# RC-car-Adruino.net
KiCad netlist of a schematic drawn in EAGLE
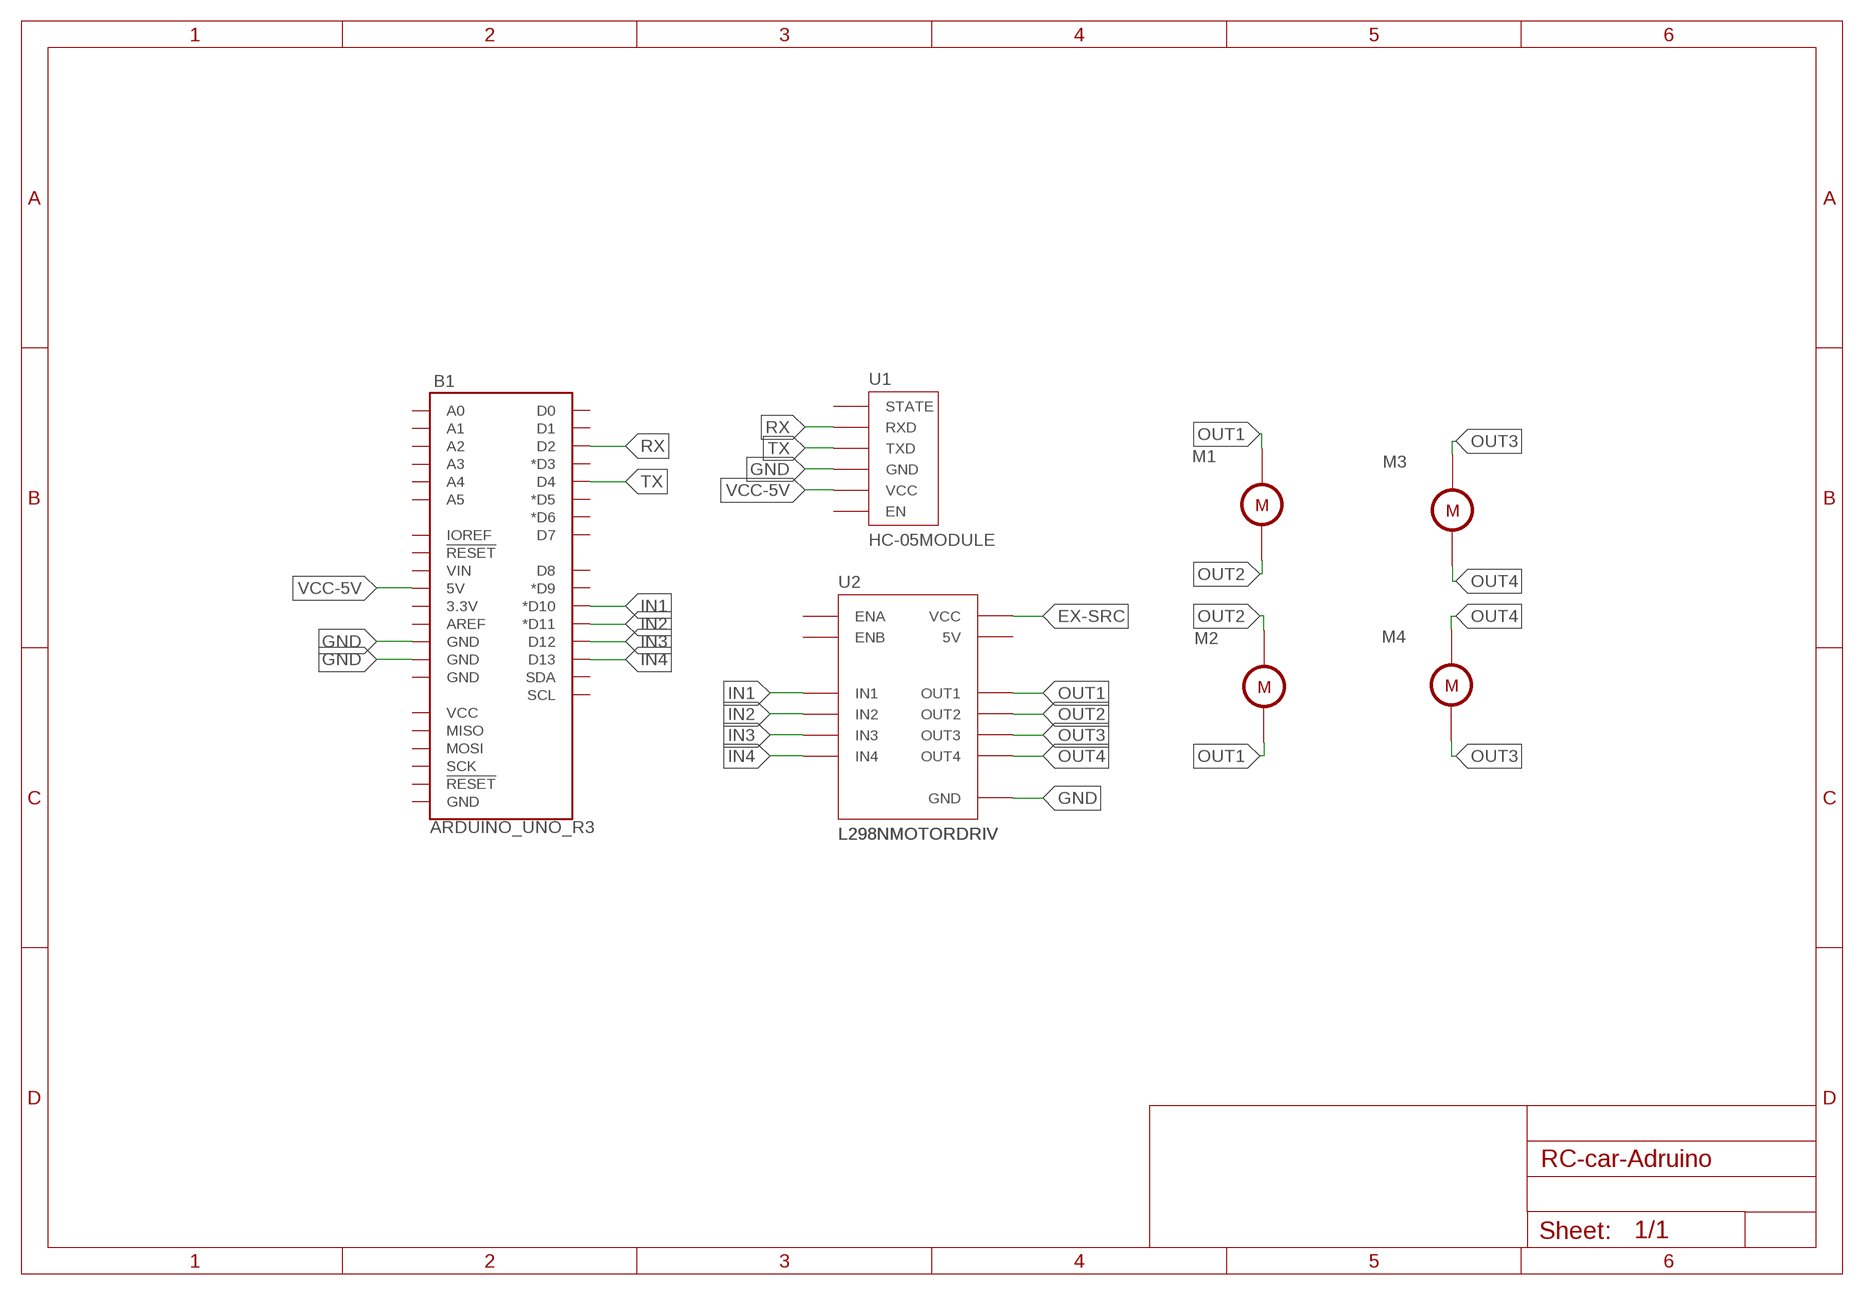
[diagram p0: schematic, sheet 1]

(export (version "E")
  (design (tool "Eeschema 10.0.6"))
  (components
    (comp (ref "B1")
      (value "ARDUINO_UNO_R3")
      (footprint "eagle-import:ARDUINO_R3")
      (libsource (lib "eagle-import") (part "ARDUINO_UNO_R3"))
    )
    (comp (ref "M1")
      (value "DC-MOTOR")
      (footprint "eagle-import:DC-MOTOR")
      (libsource (lib "eagle-import") (part "DC-MOTOR"))
    )
    (comp (ref "M2")
      (value "DC-MOTOR")
      (footprint "eagle-import:DC-MOTOR")
      (libsource (lib "eagle-import") (part "DC-MOTOR"))
    )
    (comp (ref "M3")
      (value "DC-MOTOR")
      (footprint "eagle-import:DC-MOTOR")
      (libsource (lib "eagle-import") (part "DC-MOTOR"))
    )
    (comp (ref "M4")
      (value "DC-MOTOR")
      (footprint "eagle-import:DC-MOTOR")
      (libsource (lib "eagle-import") (part "DC-MOTOR"))
    )
    (comp (ref "U1")
      (value "HC-05MODULE")
      (footprint "eagle-import:HC-05MODULE")
      (libsource (lib "eagle-import") (part "HC-05MODULE"))
    )
    (comp (ref "U2")
      (value "L298NMOTORDRIV")
      (footprint "eagle-import:L289NMOTORDRIV")
      (libsource (lib "eagle-import") (part "L298NMOTORDRIV"))
    )
  )
  (nets
    (net (code "1") (name "EX-SRC") (class "Default")
      (node (ref "U2") (pin "VCC") (pinfunction "VCC_VCC") (pintype "bidirectional"))
    )
    (net (code "2") (name "GND") (class "Default")
      (node (ref "B1") (pin "GND@3") (pinfunction "GND_GND@3") (pintype "bidirectional"))
      (node (ref "B1") (pin "GND@4") (pinfunction "GND_GND@4") (pintype "bidirectional"))
      (node (ref "U1") (pin "GND") (pinfunction "GND_GND") (pintype "bidirectional"))
      (node (ref "U2") (pin "GND") (pinfunction "GND_GND") (pintype "bidirectional"))
    )
    (net (code "3") (name "IN1") (class "Default")
      (node (ref "B1") (pin "D10") (pinfunction "*D10_D10") (pintype "bidirectional"))
      (node (ref "U2") (pin "IN1") (pinfunction "IN1_IN1") (pintype "bidirectional"))
    )
    (net (code "4") (name "IN2") (class "Default")
      (node (ref "B1") (pin "D11") (pinfunction "*D11_D11") (pintype "bidirectional"))
      (node (ref "U2") (pin "IN2") (pinfunction "IN2_IN2") (pintype "bidirectional"))
    )
    (net (code "5") (name "IN3") (class "Default")
      (node (ref "B1") (pin "D12") (pinfunction "D12_D12") (pintype "bidirectional"))
      (node (ref "U2") (pin "IN3") (pinfunction "IN3_IN3") (pintype "bidirectional"))
    )
    (net (code "6") (name "IN4") (class "Default")
      (node (ref "B1") (pin "D13") (pinfunction "D13_D13") (pintype "bidirectional"))
      (node (ref "U2") (pin "IN4") (pinfunction "IN4_IN4") (pintype "bidirectional"))
    )
    (net (code "7") (name "OUT1") (class "Default")
      (node (ref "M1") (pin "+") (pinfunction "+_+") (pintype "bidirectional"))
      (node (ref "M2") (pin "-") (pinfunction "-_-") (pintype "bidirectional"))
      (node (ref "U2") (pin "OUT1") (pinfunction "OUT1_OUT1") (pintype "bidirectional"))
    )
    (net (code "8") (name "OUT2") (class "Default")
      (node (ref "M1") (pin "-") (pinfunction "-_-") (pintype "bidirectional"))
      (node (ref "M2") (pin "+") (pinfunction "+_+") (pintype "bidirectional"))
      (node (ref "U2") (pin "OUT2") (pinfunction "OUT2_OUT2") (pintype "bidirectional"))
    )
    (net (code "9") (name "OUT3") (class "Default")
      (node (ref "M3") (pin "+") (pinfunction "+_+") (pintype "bidirectional"))
      (node (ref "M4") (pin "-") (pinfunction "-_-") (pintype "bidirectional"))
      (node (ref "U2") (pin "OUT3") (pinfunction "OUT3_OUT3") (pintype "bidirectional"))
    )
    (net (code "10") (name "OUT4") (class "Default")
      (node (ref "M3") (pin "-") (pinfunction "-_-") (pintype "bidirectional"))
      (node (ref "M4") (pin "+") (pinfunction "+_+") (pintype "bidirectional"))
      (node (ref "U2") (pin "OUT4") (pinfunction "OUT4_OUT4") (pintype "bidirectional"))
    )
    (net (code "11") (name "RX") (class "Default")
      (node (ref "B1") (pin "D2") (pinfunction "D2_D2") (pintype "bidirectional"))
      (node (ref "U1") (pin "RXD") (pinfunction "RXD_RXD") (pintype "bidirectional"))
    )
    (net (code "12") (name "TX") (class "Default")
      (node (ref "B1") (pin "D4") (pinfunction "D4_D4") (pintype "bidirectional"))
      (node (ref "U1") (pin "TXD") (pinfunction "TXD_TXD") (pintype "bidirectional"))
    )
    (net (code "13") (name "VCC-5V") (class "Default")
      (node (ref "B1") (pin "5V") (pinfunction "5V_5V") (pintype "bidirectional"))
      (node (ref "U1") (pin "VCC") (pinfunction "VCC_VCC") (pintype "bidirectional"))
    )
    (net (code "14") (name "unconnected-(B1-*D3-PadD3)") (class "Default")
      (node (ref "B1") (pin "D3") (pinfunction "*D3_D3") (pintype "bidirectional"))
    )
    (net (code "15") (name "unconnected-(B1-*D5-PadD5)") (class "Default")
      (node (ref "B1") (pin "D5") (pinfunction "*D5_D5") (pintype "bidirectional"))
    )
    (net (code "16") (name "unconnected-(B1-*D6-PadD6)") (class "Default")
      (node (ref "B1") (pin "D6") (pinfunction "*D6_D6") (pintype "bidirectional"))
    )
    (net (code "17") (name "unconnected-(B1-*D9-PadD9)") (class "Default")
      (node (ref "B1") (pin "D9") (pinfunction "*D9_D9") (pintype "bidirectional"))
    )
    (net (code "18") (name "unconnected-(B1-GND-PadGND@1)") (class "Default")
      (node (ref "B1") (pin "GND@1") (pinfunction "GND_GND@1") (pintype "bidirectional"))
    )
    (net (code "19") (name "unconnected-(B1-GND-PadGND@2)") (class "Default")
      (node (ref "B1") (pin "GND@2") (pinfunction "GND_GND@2") (pintype "bidirectional"))
    )
    (net (code "20") (name "unconnected-(B1-Pad3.3V)") (class "Default")
      (node (ref "B1") (pin "3.3V") (pinfunction "3.3V_3.3V") (pintype "bidirectional"))
    )
    (net (code "21") (name "unconnected-(B1-PadA0)") (class "Default")
      (node (ref "B1") (pin "A0") (pinfunction "A0_A0") (pintype "bidirectional"))
    )
    (net (code "22") (name "unconnected-(B1-PadA1)") (class "Default")
      (node (ref "B1") (pin "A1") (pinfunction "A1_A1") (pintype "bidirectional"))
    )
    (net (code "23") (name "unconnected-(B1-PadA2)") (class "Default")
      (node (ref "B1") (pin "A2") (pinfunction "A2_A2") (pintype "bidirectional"))
    )
    (net (code "24") (name "unconnected-(B1-PadA3)") (class "Default")
      (node (ref "B1") (pin "A3") (pinfunction "A3_A3") (pintype "bidirectional"))
    )
    (net (code "25") (name "unconnected-(B1-PadA4)") (class "Default")
      (node (ref "B1") (pin "A4") (pinfunction "A4_A4") (pintype "bidirectional"))
    )
    (net (code "26") (name "unconnected-(B1-PadA5)") (class "Default")
      (node (ref "B1") (pin "A5") (pinfunction "A5_A5") (pintype "bidirectional"))
    )
    (net (code "27") (name "unconnected-(B1-PadAREF)") (class "Default")
      (node (ref "B1") (pin "AREF") (pinfunction "AREF_AREF") (pintype "bidirectional"))
    )
    (net (code "28") (name "unconnected-(B1-PadD0)") (class "Default")
      (node (ref "B1") (pin "D0") (pinfunction "D0_D0") (pintype "bidirectional"))
    )
    (net (code "29") (name "unconnected-(B1-PadD1)") (class "Default")
      (node (ref "B1") (pin "D1") (pinfunction "D1_D1") (pintype "bidirectional"))
    )
    (net (code "30") (name "unconnected-(B1-PadD7)") (class "Default")
      (node (ref "B1") (pin "D7") (pinfunction "D7_D7") (pintype "bidirectional"))
    )
    (net (code "31") (name "unconnected-(B1-PadD8)") (class "Default")
      (node (ref "B1") (pin "D8") (pinfunction "D8_D8") (pintype "bidirectional"))
    )
    (net (code "32") (name "unconnected-(B1-PadIOREF)") (class "Default")
      (node (ref "B1") (pin "IOREF") (pinfunction "IOREF_IOREF") (pintype "bidirectional"))
    )
    (net (code "33") (name "unconnected-(B1-PadMISO)") (class "Default")
      (node (ref "B1") (pin "MISO") (pinfunction "MISO_MISO") (pintype "bidirectional"))
    )
    (net (code "34") (name "unconnected-(B1-PadMOSI)") (class "Default")
      (node (ref "B1") (pin "MOSI") (pinfunction "MOSI_MOSI") (pintype "bidirectional"))
    )
    (net (code "35") (name "unconnected-(B1-PadSCK)") (class "Default")
      (node (ref "B1") (pin "SCK") (pinfunction "SCK_SCK") (pintype "bidirectional"))
    )
    (net (code "36") (name "unconnected-(B1-PadSCL)") (class "Default")
      (node (ref "B1") (pin "SCL") (pinfunction "SCL_SCL") (pintype "bidirectional"))
    )
    (net (code "37") (name "unconnected-(B1-PadSDA)") (class "Default")
      (node (ref "B1") (pin "SDA") (pinfunction "SDA_SDA") (pintype "bidirectional"))
    )
    (net (code "38") (name "unconnected-(B1-PadVCC)") (class "Default")
      (node (ref "B1") (pin "VCC") (pinfunction "VCC_VCC") (pintype "bidirectional"))
    )
    (net (code "39") (name "unconnected-(B1-PadVIN)") (class "Default")
      (node (ref "B1") (pin "VIN") (pinfunction "VIN_VIN") (pintype "bidirectional"))
    )
    (net (code "40") (name "unconnected-(B1-~{RESET}-PadRESET@1)") (class "Default")
      (node (ref "B1") (pin "RESET@1") (pinfunction "~{RESET}_RESET@1") (pintype "bidirectional"))
    )
    (net (code "41") (name "unconnected-(B1-~{RESET}-PadRESET@2)") (class "Default")
      (node (ref "B1") (pin "RESET@2") (pinfunction "~{RESET}_RESET@2") (pintype "bidirectional"))
    )
    (net (code "42") (name "unconnected-(U1-PadEN)") (class "Default")
      (node (ref "U1") (pin "EN") (pinfunction "EN_EN") (pintype "bidirectional"))
    )
    (net (code "43") (name "unconnected-(U1-PadSTATE)") (class "Default")
      (node (ref "U1") (pin "STATE") (pinfunction "STATE_STATE") (pintype "bidirectional"))
    )
    (net (code "44") (name "unconnected-(U2-Pad5V)") (class "Default")
      (node (ref "U2") (pin "5V") (pinfunction "5V_5V") (pintype "bidirectional"))
    )
    (net (code "45") (name "unconnected-(U2-PadENA)") (class "Default")
      (node (ref "U2") (pin "ENA") (pinfunction "ENA_ENA") (pintype "bidirectional"))
    )
    (net (code "46") (name "unconnected-(U2-PadENB)") (class "Default")
      (node (ref "U2") (pin "ENB") (pinfunction "ENB_ENB") (pintype "bidirectional"))
    )
  )
)
